# smd.net
KiCad netlist of a schematic drawn in EAGLE
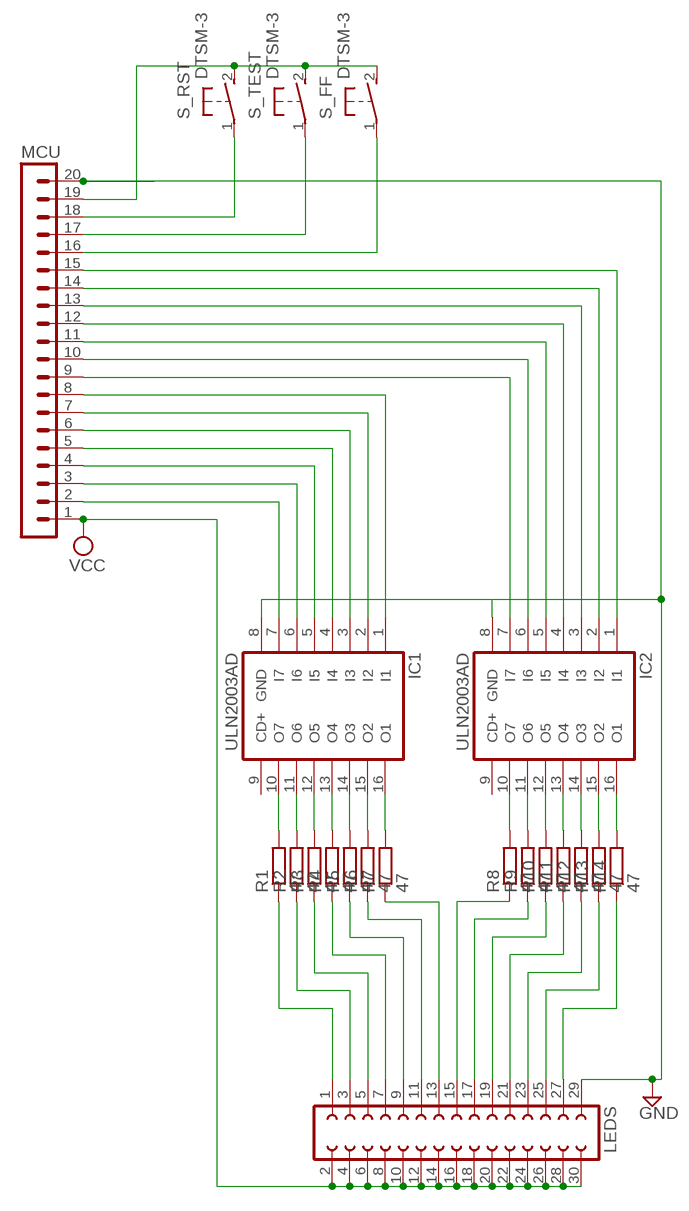
[diagram p0: schematic, sheet 1]

(export (version "E")
  (design (tool "Eeschema 10.0.6"))
  (components
    (comp (ref "IC1")
      (value "ULN2003AD")
      (footprint "eagle-import:SO16")
      (libsource (lib "eagle-import") (part "ULN2003AD"))
    )
    (comp (ref "IC2")
      (value "ULN2003AD")
      (footprint "eagle-import:SO16")
      (libsource (lib "eagle-import") (part "ULN2003AD"))
    )
    (comp (ref "LEDS")
      (value "FE15-2")
      (footprint "eagle-import:FE15-2")
      (libsource (lib "eagle-import") (part "FE15-2"))
    )
    (comp (ref "MCU")
      (value "MA20-1")
      (footprint "eagle-import:MA20-1")
      (libsource (lib "eagle-import") (part "MA20-1"))
    )
    (comp (ref "R1")
      (value "47")
      (footprint "eagle-import:M0805")
      (libsource (lib "eagle-import") (part "R-EU_M0805"))
    )
    (comp (ref "R2")
      (value "47")
      (footprint "eagle-import:M0805")
      (libsource (lib "eagle-import") (part "R-EU_M0805"))
    )
    (comp (ref "R3")
      (value "47")
      (footprint "eagle-import:M0805")
      (libsource (lib "eagle-import") (part "R-EU_M0805"))
    )
    (comp (ref "R4")
      (value "47")
      (footprint "eagle-import:M0805")
      (libsource (lib "eagle-import") (part "R-EU_M0805"))
    )
    (comp (ref "R5")
      (value "47")
      (footprint "eagle-import:M0805")
      (libsource (lib "eagle-import") (part "R-EU_M0805"))
    )
    (comp (ref "R6")
      (value "47")
      (footprint "eagle-import:M0805")
      (libsource (lib "eagle-import") (part "R-EU_M0805"))
    )
    (comp (ref "R7")
      (value "47")
      (footprint "eagle-import:M0805")
      (libsource (lib "eagle-import") (part "R-EU_M0805"))
    )
    (comp (ref "R8")
      (value "47")
      (footprint "eagle-import:M0805")
      (libsource (lib "eagle-import") (part "R-EU_M0805"))
    )
    (comp (ref "R9")
      (value "47")
      (footprint "eagle-import:M0805")
      (libsource (lib "eagle-import") (part "R-EU_M0805"))
    )
    (comp (ref "R10")
      (value "47")
      (footprint "eagle-import:M0805")
      (libsource (lib "eagle-import") (part "R-EU_M0805"))
    )
    (comp (ref "R11")
      (value "47")
      (footprint "eagle-import:M0805")
      (libsource (lib "eagle-import") (part "R-EU_M0805"))
    )
    (comp (ref "R12")
      (value "47")
      (footprint "eagle-import:M0805")
      (libsource (lib "eagle-import") (part "R-EU_M0805"))
    )
    (comp (ref "R13")
      (value "47")
      (footprint "eagle-import:M0805")
      (libsource (lib "eagle-import") (part "R-EU_M0805"))
    )
    (comp (ref "R14")
      (value "47")
      (footprint "eagle-import:M0805")
      (libsource (lib "eagle-import") (part "R-EU_M0805"))
    )
    (comp (ref "S_FF")
      (value "DTSM-3")
      (footprint "eagle-import:DTSM-3")
      (libsource (lib "eagle-import") (part "DTSM-3"))
    )
    (comp (ref "S_RST")
      (value "DTSM-3")
      (footprint "eagle-import:DTSM-3")
      (libsource (lib "eagle-import") (part "DTSM-3"))
    )
    (comp (ref "S_TEST")
      (value "DTSM-3")
      (footprint "eagle-import:DTSM-3")
      (libsource (lib "eagle-import") (part "DTSM-3"))
    )
  )
  (nets
    (net (code "1") (name "GND") (class "Default")
      (node (ref "IC1") (pin "8") (pinfunction "GND_8") (pintype "power_in"))
      (node (ref "IC2") (pin "8") (pinfunction "GND_8") (pintype "power_in"))
      (node (ref "LEDS") (pin "29") (pinfunction "29_29") (pintype "passive"))
      (node (ref "MCU") (pin "20") (pinfunction "20_20") (pintype "passive"))
    )
    (net (code "2") (name "Net-(IC1-I1)") (class "Default")
      (node (ref "IC1") (pin "1") (pinfunction "I1_1") (pintype "input"))
      (node (ref "MCU") (pin "8") (pinfunction "8_8") (pintype "passive"))
    )
    (net (code "3") (name "Net-(IC1-I2)") (class "Default")
      (node (ref "IC1") (pin "2") (pinfunction "I2_2") (pintype "input"))
      (node (ref "MCU") (pin "7") (pinfunction "7_7") (pintype "passive"))
    )
    (net (code "4") (name "Net-(IC1-I3)") (class "Default")
      (node (ref "IC1") (pin "3") (pinfunction "I3_3") (pintype "input"))
      (node (ref "MCU") (pin "6") (pinfunction "6_6") (pintype "passive"))
    )
    (net (code "5") (name "Net-(IC1-I4)") (class "Default")
      (node (ref "IC1") (pin "4") (pinfunction "I4_4") (pintype "input"))
      (node (ref "MCU") (pin "5") (pinfunction "5_5") (pintype "passive"))
    )
    (net (code "6") (name "Net-(IC1-I5)") (class "Default")
      (node (ref "IC1") (pin "5") (pinfunction "I5_5") (pintype "input"))
      (node (ref "MCU") (pin "4") (pinfunction "4_4") (pintype "passive"))
    )
    (net (code "7") (name "Net-(IC1-I6)") (class "Default")
      (node (ref "IC1") (pin "6") (pinfunction "I6_6") (pintype "input"))
      (node (ref "MCU") (pin "3") (pinfunction "3_3") (pintype "passive"))
    )
    (net (code "8") (name "Net-(IC1-I7)") (class "Default")
      (node (ref "IC1") (pin "7") (pinfunction "I7_7") (pintype "input"))
      (node (ref "MCU") (pin "2") (pinfunction "2_2") (pintype "passive"))
    )
    (net (code "9") (name "Net-(IC1-O1)") (class "Default")
      (node (ref "IC1") (pin "16") (pinfunction "O1_16") (pintype "open_collector"))
      (node (ref "R7") (pin "2") (pinfunction "2_2") (pintype "passive"))
    )
    (net (code "10") (name "Net-(IC1-O2)") (class "Default")
      (node (ref "IC1") (pin "15") (pinfunction "O2_15") (pintype "open_collector"))
      (node (ref "R6") (pin "2") (pinfunction "2_2") (pintype "passive"))
    )
    (net (code "11") (name "Net-(IC1-O3)") (class "Default")
      (node (ref "IC1") (pin "14") (pinfunction "O3_14") (pintype "open_collector"))
      (node (ref "R5") (pin "2") (pinfunction "2_2") (pintype "passive"))
    )
    (net (code "12") (name "Net-(IC1-O4)") (class "Default")
      (node (ref "IC1") (pin "13") (pinfunction "O4_13") (pintype "open_collector"))
      (node (ref "R4") (pin "2") (pinfunction "2_2") (pintype "passive"))
    )
    (net (code "13") (name "Net-(IC1-O5)") (class "Default")
      (node (ref "IC1") (pin "12") (pinfunction "O5_12") (pintype "open_collector"))
      (node (ref "R3") (pin "2") (pinfunction "2_2") (pintype "passive"))
    )
    (net (code "14") (name "Net-(IC1-O6)") (class "Default")
      (node (ref "IC1") (pin "11") (pinfunction "O6_11") (pintype "open_collector"))
      (node (ref "R2") (pin "2") (pinfunction "2_2") (pintype "passive"))
    )
    (net (code "15") (name "Net-(IC1-O7)") (class "Default")
      (node (ref "IC1") (pin "10") (pinfunction "O7_10") (pintype "open_collector"))
      (node (ref "R1") (pin "2") (pinfunction "2_2") (pintype "passive"))
    )
    (net (code "16") (name "Net-(IC2-I1)") (class "Default")
      (node (ref "IC2") (pin "1") (pinfunction "I1_1") (pintype "input"))
      (node (ref "MCU") (pin "15") (pinfunction "15_15") (pintype "passive"))
    )
    (net (code "17") (name "Net-(IC2-I2)") (class "Default")
      (node (ref "IC2") (pin "2") (pinfunction "I2_2") (pintype "input"))
      (node (ref "MCU") (pin "14") (pinfunction "14_14") (pintype "passive"))
    )
    (net (code "18") (name "Net-(IC2-I3)") (class "Default")
      (node (ref "IC2") (pin "3") (pinfunction "I3_3") (pintype "input"))
      (node (ref "MCU") (pin "13") (pinfunction "13_13") (pintype "passive"))
    )
    (net (code "19") (name "Net-(IC2-I4)") (class "Default")
      (node (ref "IC2") (pin "4") (pinfunction "I4_4") (pintype "input"))
      (node (ref "MCU") (pin "12") (pinfunction "12_12") (pintype "passive"))
    )
    (net (code "20") (name "Net-(IC2-I5)") (class "Default")
      (node (ref "IC2") (pin "5") (pinfunction "I5_5") (pintype "input"))
      (node (ref "MCU") (pin "11") (pinfunction "11_11") (pintype "passive"))
    )
    (net (code "21") (name "Net-(IC2-I6)") (class "Default")
      (node (ref "IC2") (pin "6") (pinfunction "I6_6") (pintype "input"))
      (node (ref "MCU") (pin "10") (pinfunction "10_10") (pintype "passive"))
    )
    (net (code "22") (name "Net-(IC2-I7)") (class "Default")
      (node (ref "IC2") (pin "7") (pinfunction "I7_7") (pintype "input"))
      (node (ref "MCU") (pin "9") (pinfunction "9_9") (pintype "passive"))
    )
    (net (code "23") (name "Net-(IC2-O1)") (class "Default")
      (node (ref "IC2") (pin "16") (pinfunction "O1_16") (pintype "open_collector"))
      (node (ref "R14") (pin "2") (pinfunction "2_2") (pintype "passive"))
    )
    (net (code "24") (name "Net-(IC2-O2)") (class "Default")
      (node (ref "IC2") (pin "15") (pinfunction "O2_15") (pintype "open_collector"))
      (node (ref "R13") (pin "2") (pinfunction "2_2") (pintype "passive"))
    )
    (net (code "25") (name "Net-(IC2-O3)") (class "Default")
      (node (ref "IC2") (pin "14") (pinfunction "O3_14") (pintype "open_collector"))
      (node (ref "R12") (pin "2") (pinfunction "2_2") (pintype "passive"))
    )
    (net (code "26") (name "Net-(IC2-O4)") (class "Default")
      (node (ref "IC2") (pin "13") (pinfunction "O4_13") (pintype "open_collector"))
      (node (ref "R11") (pin "2") (pinfunction "2_2") (pintype "passive"))
    )
    (net (code "27") (name "Net-(IC2-O5)") (class "Default")
      (node (ref "IC2") (pin "12") (pinfunction "O5_12") (pintype "open_collector"))
      (node (ref "R10") (pin "2") (pinfunction "2_2") (pintype "passive"))
    )
    (net (code "28") (name "Net-(IC2-O6)") (class "Default")
      (node (ref "IC2") (pin "11") (pinfunction "O6_11") (pintype "open_collector"))
      (node (ref "R9") (pin "2") (pinfunction "2_2") (pintype "passive"))
    )
    (net (code "29") (name "Net-(IC2-O7)") (class "Default")
      (node (ref "IC2") (pin "10") (pinfunction "O7_10") (pintype "open_collector"))
      (node (ref "R8") (pin "2") (pinfunction "2_2") (pintype "passive"))
    )
    (net (code "30") (name "Net-(LEDS-Pad1)") (class "Default")
      (node (ref "LEDS") (pin "1") (pinfunction "1_1") (pintype "passive"))
      (node (ref "R1") (pin "1") (pinfunction "1_1") (pintype "passive"))
    )
    (net (code "31") (name "Net-(LEDS-Pad3)") (class "Default")
      (node (ref "LEDS") (pin "3") (pinfunction "3_3") (pintype "passive"))
      (node (ref "R2") (pin "1") (pinfunction "1_1") (pintype "passive"))
    )
    (net (code "32") (name "Net-(LEDS-Pad5)") (class "Default")
      (node (ref "LEDS") (pin "5") (pinfunction "5_5") (pintype "passive"))
      (node (ref "R3") (pin "1") (pinfunction "1_1") (pintype "passive"))
    )
    (net (code "33") (name "Net-(LEDS-Pad7)") (class "Default")
      (node (ref "LEDS") (pin "7") (pinfunction "7_7") (pintype "passive"))
      (node (ref "R4") (pin "1") (pinfunction "1_1") (pintype "passive"))
    )
    (net (code "34") (name "Net-(LEDS-Pad9)") (class "Default")
      (node (ref "LEDS") (pin "9") (pinfunction "9_9") (pintype "passive"))
      (node (ref "R5") (pin "1") (pinfunction "1_1") (pintype "passive"))
    )
    (net (code "35") (name "Net-(LEDS-Pad11)") (class "Default")
      (node (ref "LEDS") (pin "11") (pinfunction "11_11") (pintype "passive"))
      (node (ref "R6") (pin "1") (pinfunction "1_1") (pintype "passive"))
    )
    (net (code "36") (name "Net-(LEDS-Pad13)") (class "Default")
      (node (ref "LEDS") (pin "13") (pinfunction "13_13") (pintype "passive"))
      (node (ref "R7") (pin "1") (pinfunction "1_1") (pintype "passive"))
    )
    (net (code "37") (name "Net-(LEDS-Pad15)") (class "Default")
      (node (ref "LEDS") (pin "15") (pinfunction "15_15") (pintype "passive"))
      (node (ref "R8") (pin "1") (pinfunction "1_1") (pintype "passive"))
    )
    (net (code "38") (name "Net-(LEDS-Pad17)") (class "Default")
      (node (ref "LEDS") (pin "17") (pinfunction "17_17") (pintype "passive"))
      (node (ref "R9") (pin "1") (pinfunction "1_1") (pintype "passive"))
    )
    (net (code "39") (name "Net-(LEDS-Pad19)") (class "Default")
      (node (ref "LEDS") (pin "19") (pinfunction "19_19") (pintype "passive"))
      (node (ref "R10") (pin "1") (pinfunction "1_1") (pintype "passive"))
    )
    (net (code "40") (name "Net-(LEDS-Pad21)") (class "Default")
      (node (ref "LEDS") (pin "21") (pinfunction "21_21") (pintype "passive"))
      (node (ref "R11") (pin "1") (pinfunction "1_1") (pintype "passive"))
    )
    (net (code "41") (name "Net-(LEDS-Pad23)") (class "Default")
      (node (ref "LEDS") (pin "23") (pinfunction "23_23") (pintype "passive"))
      (node (ref "R12") (pin "1") (pinfunction "1_1") (pintype "passive"))
    )
    (net (code "42") (name "Net-(LEDS-Pad25)") (class "Default")
      (node (ref "LEDS") (pin "25") (pinfunction "25_25") (pintype "passive"))
      (node (ref "R13") (pin "1") (pinfunction "1_1") (pintype "passive"))
    )
    (net (code "43") (name "Net-(LEDS-Pad27)") (class "Default")
      (node (ref "LEDS") (pin "27") (pinfunction "27_27") (pintype "passive"))
      (node (ref "R14") (pin "1") (pinfunction "1_1") (pintype "passive"))
    )
    (net (code "44") (name "Net-(MCU-Pad16)") (class "Default")
      (node (ref "MCU") (pin "16") (pinfunction "16_16") (pintype "passive"))
      (node (ref "S_FF") (pin "1") (pinfunction "1_1") (pintype "passive"))
    )
    (net (code "45") (name "Net-(MCU-Pad17)") (class "Default")
      (node (ref "MCU") (pin "17") (pinfunction "17_17") (pintype "passive"))
      (node (ref "S_TEST") (pin "1") (pinfunction "1_1") (pintype "passive"))
    )
    (net (code "46") (name "Net-(MCU-Pad18)") (class "Default")
      (node (ref "MCU") (pin "18") (pinfunction "18_18") (pintype "passive"))
      (node (ref "S_RST") (pin "1") (pinfunction "1_1") (pintype "passive"))
    )
    (net (code "47") (name "Net-(MCU-Pad19)") (class "Default")
      (node (ref "MCU") (pin "19") (pinfunction "19_19") (pintype "passive"))
      (node (ref "S_FF") (pin "2") (pinfunction "2_2") (pintype "passive"))
      (node (ref "S_RST") (pin "2") (pinfunction "2_2") (pintype "passive"))
      (node (ref "S_TEST") (pin "2") (pinfunction "2_2") (pintype "passive"))
    )
    (net (code "48") (name "VCC") (class "Default")
      (node (ref "LEDS") (pin "10") (pinfunction "10_10") (pintype "passive"))
      (node (ref "LEDS") (pin "12") (pinfunction "12_12") (pintype "passive"))
      (node (ref "LEDS") (pin "14") (pinfunction "14_14") (pintype "passive"))
      (node (ref "LEDS") (pin "16") (pinfunction "16_16") (pintype "passive"))
      (node (ref "LEDS") (pin "18") (pinfunction "18_18") (pintype "passive"))
      (node (ref "LEDS") (pin "2") (pinfunction "2_2") (pintype "passive"))
      (node (ref "LEDS") (pin "20") (pinfunction "20_20") (pintype "passive"))
      (node (ref "LEDS") (pin "22") (pinfunction "22_22") (pintype "passive"))
      (node (ref "LEDS") (pin "24") (pinfunction "24_24") (pintype "passive"))
      (node (ref "LEDS") (pin "26") (pinfunction "26_26") (pintype "passive"))
      (node (ref "LEDS") (pin "28") (pinfunction "28_28") (pintype "passive"))
      (node (ref "LEDS") (pin "30") (pinfunction "30_30") (pintype "passive"))
      (node (ref "LEDS") (pin "4") (pinfunction "4_4") (pintype "passive"))
      (node (ref "LEDS") (pin "6") (pinfunction "6_6") (pintype "passive"))
      (node (ref "LEDS") (pin "8") (pinfunction "8_8") (pintype "passive"))
      (node (ref "MCU") (pin "1") (pinfunction "1_1") (pintype "passive"))
    )
    (net (code "49") (name "unconnected-(IC1-CD+-Pad9)") (class "Default")
      (node (ref "IC1") (pin "9") (pinfunction "CD+_9") (pintype "passive"))
    )
    (net (code "50") (name "unconnected-(IC2-CD+-Pad9)") (class "Default")
      (node (ref "IC2") (pin "9") (pinfunction "CD+_9") (pintype "passive"))
    )
  )
)
